# moto2.net
KiCad netlist of a schematic drawn in Altium Designer
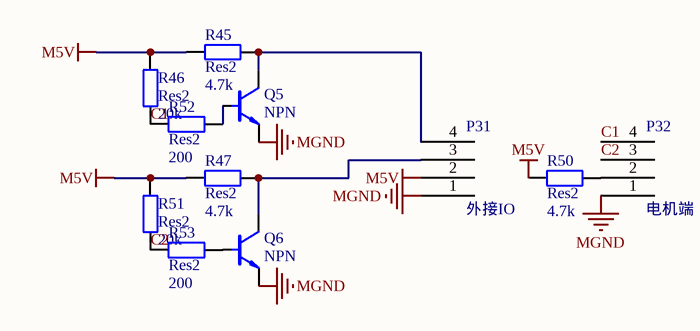
[diagram p0: moto2.SchDoc]

(export (version "E")
  (design (tool "Eeschema 10.0.6"))
  (components
    (comp (ref "P31") (value "外接IO") (footprint "4针贴片接头2.0") (libsource (lib "ros_car_lib") (part "4线焊接点")))
    (comp (ref "P32") (value "电机端") (footprint "4针贴片接头2.0") (libsource (lib "ros_car_lib") (part "4线焊接点")))
    (comp (ref "Q5") (value "NPN") (footprint "LC-SOT-23") (libsource (lib "ARAMYLIB") (part "NPN")))
    (comp (ref "Q6") (value "NPN") (footprint "LC-SOT-23") (libsource (lib "ARAMYLIB") (part "NPN")))
    (comp (ref "R45")
      (value "Res2")
      (footprint "LC-0603_R")
      (description "Resistor")
      (fields (field (name "ALTIUM_VALUE") "4.7k") (field (name "PUBLISHER") "Altium Limited"))
      (libsource (lib "") (part "Res2_2"))
    )
    (comp (ref "R46")
      (value "Res2")
      (footprint "LC-0603_R")
      (description "Resistor")
      (fields (field (name "ALTIUM_VALUE") "20k") (field (name "PUBLISHER") "Altium Limited"))
      (libsource (lib "Miscellaneous Devices") (part "Res2"))
    )
    (comp (ref "R47")
      (value "Res2")
      (footprint "LC-0603_R")
      (description "Resistor")
      (fields (field (name "ALTIUM_VALUE") "4.7k") (field (name "PUBLISHER") "Altium Limited"))
      (libsource (lib "") (part "Res2_2"))
    )
    (comp (ref "R50")
      (value "Res2")
      (footprint "LC-0603_R")
      (description "Resistor")
      (fields (field (name "ALTIUM_VALUE") "4.7k") (field (name "PUBLISHER") "Altium Limited"))
      (libsource (lib "") (part "Res2_2"))
    )
    (comp (ref "R51")
      (value "Res2")
      (footprint "LC-0603_R")
      (description "Resistor")
      (fields (field (name "ALTIUM_VALUE") "20k") (field (name "PUBLISHER") "Altium Limited"))
      (libsource (lib "Miscellaneous Devices") (part "Res2"))
    )
    (comp (ref "R52")
      (value "Res2")
      (footprint "LC-0603_R")
      (description "Resistor")
      (fields (field (name "ALTIUM_VALUE") "200") (field (name "PUBLISHER") "Altium Limited"))
      (libsource (lib "") (part "Res2_1"))
    )
    (comp (ref "R53")
      (value "Res2")
      (footprint "LC-0603_R")
      (description "Resistor")
      (fields (field (name "ALTIUM_VALUE") "200") (field (name "PUBLISHER") "Altium Limited"))
      (libsource (lib "") (part "Res2_1"))
    )
  )
  (nets
    (net (code "1") (name "/C1") (class "Default")
      (node (ref "P32") (pin "4") (pintype "passive"))
      (node (ref "R46") (pin "1") (pinfunction "1_1") (pintype "passive"))
      (node (ref "R52") (pin "2") (pinfunction "2_2") (pintype "passive"))
    )
    (net (code "2") (name "/C2") (class "Default")
      (node (ref "P32") (pin "3") (pintype "passive"))
      (node (ref "R51") (pin "1") (pinfunction "1_1") (pintype "passive"))
      (node (ref "R53") (pin "2") (pinfunction "2_2") (pintype "passive"))
    )
    (net (code "3") (name "M5V") (class "Default")
      (node (ref "P31") (pin "2") (pintype "passive"))
      (node (ref "R45") (pin "1") (pinfunction "1_1") (pintype "passive"))
      (node (ref "R46") (pin "2") (pinfunction "2_2") (pintype "passive"))
      (node (ref "R47") (pin "1") (pinfunction "1_1") (pintype "passive"))
      (node (ref "R50") (pin "1") (pinfunction "1_1") (pintype "passive"))
      (node (ref "R51") (pin "2") (pinfunction "2_2") (pintype "passive"))
    )
    (net (code "4") (name "MGND") (class "Default")
      (node (ref "P31") (pin "1") (pintype "power_in"))
      (node (ref "P32") (pin "1") (pintype "power_in"))
      (node (ref "Q5") (pin "E") (pinfunction "e_E") (pintype "passive"))
      (node (ref "Q6") (pin "E") (pinfunction "e_E") (pintype "passive"))
    )
    (net (code "5") (name "Net-(P32-Pad2)") (class "Default")
      (node (ref "P32") (pin "2") (pintype "passive"))
      (node (ref "R50") (pin "2") (pinfunction "2_2") (pintype "passive"))
    )
    (net (code "6") (name "Net-(Q5-b)") (class "Default")
      (node (ref "Q5") (pin "B") (pinfunction "b_B") (pintype "passive"))
      (node (ref "R52") (pin "1") (pinfunction "1_1") (pintype "passive"))
    )
    (net (code "7") (name "Net-(Q5-c)") (class "Default")
      (node (ref "P31") (pin "4") (pintype "passive"))
      (node (ref "Q5") (pin "C") (pinfunction "c_C") (pintype "passive"))
      (node (ref "R45") (pin "2") (pinfunction "2_2") (pintype "passive"))
    )
    (net (code "8") (name "Net-(Q6-b)") (class "Default")
      (node (ref "Q6") (pin "B") (pinfunction "b_B") (pintype "passive"))
      (node (ref "R53") (pin "1") (pinfunction "1_1") (pintype "passive"))
    )
    (net (code "9") (name "Net-(Q6-c)") (class "Default")
      (node (ref "P31") (pin "3") (pintype "passive"))
      (node (ref "Q6") (pin "C") (pinfunction "c_C") (pintype "passive"))
      (node (ref "R47") (pin "2") (pinfunction "2_2") (pintype "passive"))
    )
  )
)
